# Schematic.net
KiCad netlist of a schematic drawn in EasyEDA
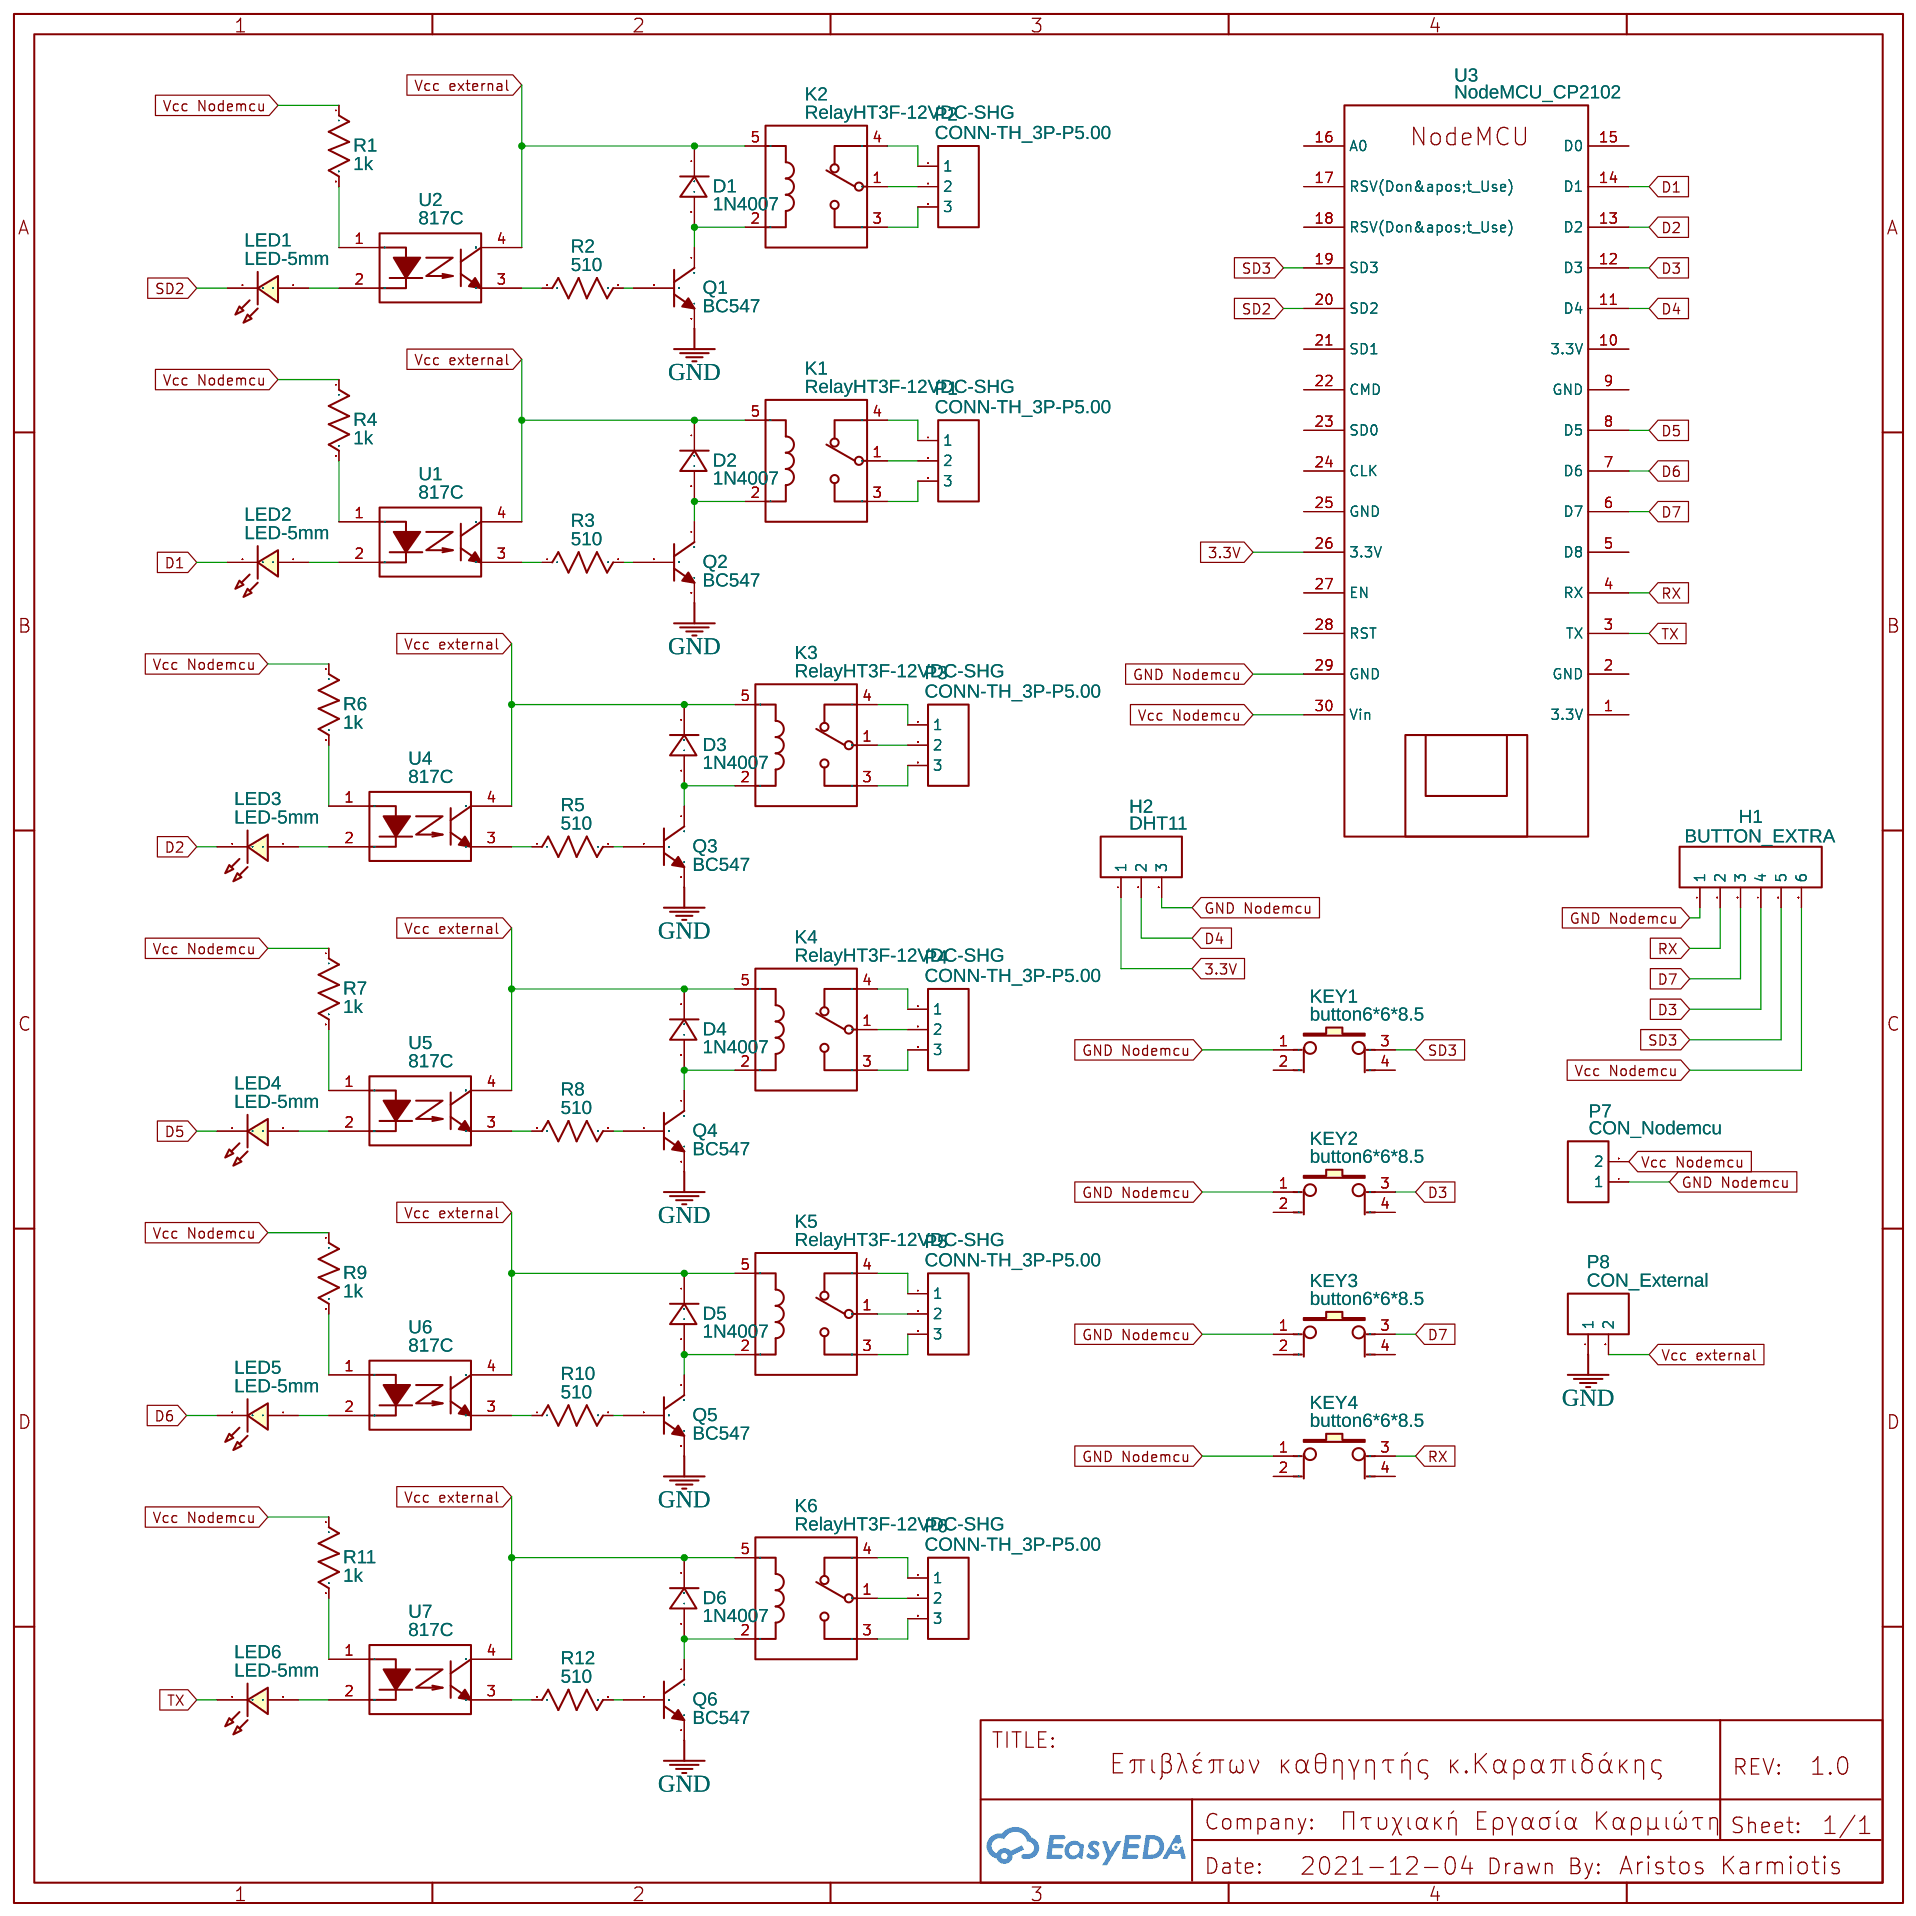
[diagram p0: schematic sheet]

(export (version "E")
  (design (tool "Eeschema 10.0.6"))
  (components
    (comp (ref "D1")
      (value "1N4007")
      (fields (field (name "BOM_Manufacturer Part") "1N4007G-K") (field (name "BOM_Supplier Part") "C410859"))
      (libsource (lib "") (part "1N4007G-K"))
    )
    (comp (ref "D2")
      (value "1N4007")
      (fields (field (name "BOM_Manufacturer Part") "1N4007G-K") (field (name "BOM_Supplier Part") "C410859"))
      (libsource (lib "") (part "1N4007G-K"))
    )
    (comp (ref "D3")
      (value "1N4007")
      (fields (field (name "BOM_Manufacturer Part") "1N4007G-K") (field (name "BOM_Supplier Part") "C410859"))
      (libsource (lib "") (part "1N4007G-K"))
    )
    (comp (ref "D4")
      (value "1N4007")
      (fields (field (name "BOM_Manufacturer Part") "1N4007G-K") (field (name "BOM_Supplier Part") "C410859"))
      (libsource (lib "") (part "1N4007G-K"))
    )
    (comp (ref "D5")
      (value "1N4007")
      (fields (field (name "BOM_Manufacturer Part") "1N4007G-K") (field (name "BOM_Supplier Part") "C410859"))
      (libsource (lib "") (part "1N4007G-K"))
    )
    (comp (ref "D6")
      (value "1N4007")
      (fields (field (name "BOM_Manufacturer Part") "1N4007G-K") (field (name "BOM_Supplier Part") "C410859"))
      (libsource (lib "") (part "1N4007G-K"))
    )
    (comp (ref "H1")
      (value "BUTTON_EXTRA")
      (fields (field (name "BOM_Supplier Part") "C40877"))
      (libsource (lib "") (part "HDR-F-2.54_1x6"))
    )
    (comp (ref "H2")
      (value "DHT11")
      (fields (field (name "BOM_Supplier Part") "C146690"))
      (libsource (lib "") (part "HDR-F-2.54_1x3"))
    )
    (comp (ref "K1")
      (value "RelayHT3F-12VDC-SHG")
      (fields (field (name "BOM_Supplier Part") "C22022"))
      (libsource (lib "") (part "RelayHT3F-12VDC-SHG"))
    )
    (comp (ref "K2")
      (value "RelayHT3F-12VDC-SHG")
      (fields (field (name "BOM_Supplier Part") "C22022"))
      (libsource (lib "") (part "RelayHT3F-12VDC-SHG"))
    )
    (comp (ref "K3")
      (value "RelayHT3F-12VDC-SHG")
      (fields (field (name "BOM_Supplier Part") "C22022"))
      (libsource (lib "") (part "RelayHT3F-12VDC-SHG"))
    )
    (comp (ref "K4")
      (value "RelayHT3F-12VDC-SHG")
      (fields (field (name "BOM_Supplier Part") "C22022"))
      (libsource (lib "") (part "RelayHT3F-12VDC-SHG"))
    )
    (comp (ref "K5")
      (value "RelayHT3F-12VDC-SHG")
      (fields (field (name "BOM_Supplier Part") "C22022"))
      (libsource (lib "") (part "RelayHT3F-12VDC-SHG"))
    )
    (comp (ref "K6")
      (value "RelayHT3F-12VDC-SHG")
      (fields (field (name "BOM_Supplier Part") "C22022"))
      (libsource (lib "") (part "RelayHT3F-12VDC-SHG"))
    )
    (comp (ref "KEY1")
      (value "button6*6*8.5")
      (fields (field (name "BOM_Supplier Part") "C59980"))
      (libsource (lib "") (part "button6*6*8.5"))
    )
    (comp (ref "KEY2")
      (value "button6*6*8.5")
      (fields (field (name "BOM_Supplier Part") "C59980"))
      (libsource (lib "") (part "button6*6*8.5"))
    )
    (comp (ref "KEY3")
      (value "button6*6*8.5")
      (fields (field (name "BOM_Supplier Part") "C59980"))
      (libsource (lib "") (part "button6*6*8.5"))
    )
    (comp (ref "KEY4")
      (value "button6*6*8.5")
      (fields (field (name "BOM_Supplier Part") "C59980"))
      (libsource (lib "") (part "button6*6*8.5"))
    )
    (comp (ref "LED1")
      (value "LED-5mm")
      (fields
        (field (name "BOM_Manufacturer Part") "333-2SURD/S530-A3")
        (field (name "BOM_Supplier Part") "C87271")
      )
      (libsource (lib "") (part "LED-TH-5mm_R"))
    )
    (comp (ref "LED2")
      (value "LED-5mm")
      (fields
        (field (name "BOM_Manufacturer Part") "333-2SURD/S530-A3")
        (field (name "BOM_Supplier Part") "C87271")
      )
      (libsource (lib "") (part "LED-TH-5mm_R"))
    )
    (comp (ref "LED3")
      (value "LED-5mm")
      (fields
        (field (name "BOM_Manufacturer Part") "333-2SURD/S530-A3")
        (field (name "BOM_Supplier Part") "C87271")
      )
      (libsource (lib "") (part "LED-TH-5mm_R"))
    )
    (comp (ref "LED4")
      (value "LED-5mm")
      (fields
        (field (name "BOM_Manufacturer Part") "333-2SURD/S530-A3")
        (field (name "BOM_Supplier Part") "C87271")
      )
      (libsource (lib "") (part "LED-TH-5mm_R"))
    )
    (comp (ref "LED5")
      (value "LED-5mm")
      (fields
        (field (name "BOM_Manufacturer Part") "333-2SURD/S530-A3")
        (field (name "BOM_Supplier Part") "C87271")
      )
      (libsource (lib "") (part "LED-TH-5mm_R"))
    )
    (comp (ref "LED6")
      (value "LED-5mm")
      (fields
        (field (name "BOM_Manufacturer Part") "333-2SURD/S530-A3")
        (field (name "BOM_Supplier Part") "C87271")
      )
      (libsource (lib "") (part "LED-TH-5mm_R"))
    )
    (comp (ref "P1") (value "CONN-TH_3P-P5.00") (libsource (lib "") (part "CONN-TH_3P-P5.00")))
    (comp (ref "P2") (value "CONN-TH_3P-P5.00") (libsource (lib "") (part "CONN-TH_3P-P5.00")))
    (comp (ref "P3") (value "CONN-TH_3P-P5.00") (libsource (lib "") (part "CONN-TH_3P-P5.00")))
    (comp (ref "P4") (value "CONN-TH_3P-P5.00") (libsource (lib "") (part "CONN-TH_3P-P5.00")))
    (comp (ref "P5") (value "CONN-TH_3P-P5.00") (libsource (lib "") (part "CONN-TH_3P-P5.00")))
    (comp (ref "P6") (value "CONN-TH_3P-P5.00") (libsource (lib "") (part "CONN-TH_3P-P5.00")))
    (comp (ref "P7") (value "CON_Nodemcu") (libsource (lib "") (part "CONN-TH_2P-P5.00_1")))
    (comp (ref "P8") (value "CON_External") (libsource (lib "") (part "CONN-TH_2P-P5.00")))
    (comp (ref "Q1")
      (value "BC547")
      (fields (field (name "BOM_Manufacturer Part") "BC547BTF") (field (name "BOM_Supplier Part") "C900798"))
      (libsource (lib "") (part "BC547BTF"))
    )
    (comp (ref "Q2")
      (value "BC547")
      (fields (field (name "BOM_Manufacturer Part") "BC547BTF") (field (name "BOM_Supplier Part") "C900798"))
      (libsource (lib "") (part "BC547BTF"))
    )
    (comp (ref "Q3")
      (value "BC547")
      (fields (field (name "BOM_Manufacturer Part") "BC547BTF") (field (name "BOM_Supplier Part") "C900798"))
      (libsource (lib "") (part "BC547BTF"))
    )
    (comp (ref "Q4")
      (value "BC547")
      (fields (field (name "BOM_Manufacturer Part") "BC547BTF") (field (name "BOM_Supplier Part") "C900798"))
      (libsource (lib "") (part "BC547BTF"))
    )
    (comp (ref "Q5")
      (value "BC547")
      (fields (field (name "BOM_Manufacturer Part") "BC547BTF") (field (name "BOM_Supplier Part") "C900798"))
      (libsource (lib "") (part "BC547BTF"))
    )
    (comp (ref "Q6")
      (value "BC547")
      (fields (field (name "BOM_Manufacturer Part") "BC547BTF") (field (name "BOM_Supplier Part") "C900798"))
      (libsource (lib "") (part "BC547BTF"))
    )
    (comp (ref "R1") (value "1k") (libsource (lib "") (part "R_AXIAL-0.4_US_1")))
    (comp (ref "R2") (value "510") (libsource (lib "") (part "R_AXIAL-0.4_US")))
    (comp (ref "R3") (value "510") (libsource (lib "") (part "R_AXIAL-0.4_US")))
    (comp (ref "R4") (value "1k") (libsource (lib "") (part "R_AXIAL-0.4_US_1")))
    (comp (ref "R5") (value "510") (libsource (lib "") (part "R_AXIAL-0.4_US")))
    (comp (ref "R6") (value "1k") (libsource (lib "") (part "R_AXIAL-0.4_US_1")))
    (comp (ref "R7") (value "1k") (libsource (lib "") (part "R_AXIAL-0.4_US_1")))
    (comp (ref "R8") (value "510") (libsource (lib "") (part "R_AXIAL-0.4_US")))
    (comp (ref "R9") (value "1k") (libsource (lib "") (part "R_AXIAL-0.4_US_1")))
    (comp (ref "R10") (value "510") (libsource (lib "") (part "R_AXIAL-0.4_US")))
    (comp (ref "R11") (value "1k") (libsource (lib "") (part "R_AXIAL-0.4_US_1")))
    (comp (ref "R12") (value "510") (libsource (lib "") (part "R_AXIAL-0.4_US")))
    (comp (ref "U1")
      (value "817C")
      (fields
        (field (name "BOM_Manufacturer Part") "FOD817C300")
        (field (name "BOM_Supplier Part") "C124472")
      )
      (libsource (lib "") (part "FOD817C300"))
    )
    (comp (ref "U2")
      (value "817C")
      (fields
        (field (name "BOM_Manufacturer Part") "FOD817C300")
        (field (name "BOM_Supplier Part") "C124472")
      )
      (libsource (lib "") (part "FOD817C300"))
    )
    (comp (ref "U3") (value "NodeMCU_CP2102") (libsource (lib "") (part "NodeMCU_CP2102")))
    (comp (ref "U4")
      (value "817C")
      (fields
        (field (name "BOM_Manufacturer Part") "FOD817C300")
        (field (name "BOM_Supplier Part") "C124472")
      )
      (libsource (lib "") (part "FOD817C300"))
    )
    (comp (ref "U5")
      (value "817C")
      (fields
        (field (name "BOM_Manufacturer Part") "FOD817C300")
        (field (name "BOM_Supplier Part") "C124472")
      )
      (libsource (lib "") (part "FOD817C300"))
    )
    (comp (ref "U6")
      (value "817C")
      (fields
        (field (name "BOM_Manufacturer Part") "FOD817C300")
        (field (name "BOM_Supplier Part") "C124472")
      )
      (libsource (lib "") (part "FOD817C300"))
    )
    (comp (ref "U7")
      (value "817C")
      (fields
        (field (name "BOM_Manufacturer Part") "FOD817C300")
        (field (name "BOM_Supplier Part") "C124472")
      )
      (libsource (lib "") (part "FOD817C300"))
    )
  )
  (nets
    (net (code "1") (name "3.3V") (class "Default")
      (node (ref "H2") (pin "1") (pinfunction "1_1") (pintype "input"))
      (node (ref "U3") (pin "26") (pinfunction "3.3V_26") (pintype "unspecified"))
    )
    (net (code "2") (name "D1") (class "Default")
      (node (ref "LED2") (pin "2") (pinfunction "2_2") (pintype "unspecified"))
      (node (ref "U3") (pin "14") (pinfunction "D1_14") (pintype "unspecified"))
    )
    (net (code "3") (name "D2") (class "Default")
      (node (ref "LED3") (pin "2") (pinfunction "2_2") (pintype "unspecified"))
      (node (ref "U3") (pin "13") (pinfunction "D2_13") (pintype "unspecified"))
    )
    (net (code "4") (name "D3") (class "Default")
      (node (ref "H1") (pin "4") (pinfunction "4_4") (pintype "input"))
      (node (ref "KEY2") (pin "3") (pinfunction "3_3") (pintype "input"))
      (node (ref "U3") (pin "12") (pinfunction "D3_12") (pintype "unspecified"))
    )
    (net (code "5") (name "D4") (class "Default")
      (node (ref "H2") (pin "2") (pinfunction "2_2") (pintype "input"))
      (node (ref "U3") (pin "11") (pinfunction "D4_11") (pintype "unspecified"))
    )
    (net (code "6") (name "D5") (class "Default")
      (node (ref "LED4") (pin "2") (pinfunction "2_2") (pintype "unspecified"))
      (node (ref "U3") (pin "8") (pinfunction "D5_8") (pintype "unspecified"))
    )
    (net (code "7") (name "D6") (class "Default")
      (node (ref "LED5") (pin "2") (pinfunction "2_2") (pintype "unspecified"))
      (node (ref "U3") (pin "7") (pinfunction "D6_7") (pintype "unspecified"))
    )
    (net (code "8") (name "D7") (class "Default")
      (node (ref "H1") (pin "3") (pinfunction "3_3") (pintype "input"))
      (node (ref "KEY3") (pin "3") (pinfunction "3_3") (pintype "input"))
      (node (ref "U3") (pin "6") (pinfunction "D7_6") (pintype "unspecified"))
    )
    (net (code "9") (name "GND") (class "Default")
      (node (ref "P8") (pin "1") (pinfunction "1_1") (pintype "unspecified"))
      (node (ref "Q1") (pin "3") (pinfunction "E_3") (pintype "unspecified"))
      (node (ref "Q2") (pin "3") (pinfunction "E_3") (pintype "unspecified"))
      (node (ref "Q3") (pin "3") (pinfunction "E_3") (pintype "unspecified"))
      (node (ref "Q4") (pin "3") (pinfunction "E_3") (pintype "unspecified"))
      (node (ref "Q5") (pin "3") (pinfunction "E_3") (pintype "unspecified"))
      (node (ref "Q6") (pin "3") (pinfunction "E_3") (pintype "unspecified"))
    )
    (net (code "10") (name "GND Nodemcu") (class "Default")
      (node (ref "H1") (pin "1") (pinfunction "1_1") (pintype "input"))
      (node (ref "H2") (pin "3") (pinfunction "3_3") (pintype "input"))
      (node (ref "KEY1") (pin "1") (pinfunction "1_1") (pintype "input"))
      (node (ref "KEY2") (pin "1") (pinfunction "1_1") (pintype "input"))
      (node (ref "KEY3") (pin "1") (pinfunction "1_1") (pintype "input"))
      (node (ref "KEY4") (pin "1") (pinfunction "1_1") (pintype "input"))
      (node (ref "P7") (pin "1") (pinfunction "1_1") (pintype "unspecified"))
      (node (ref "U3") (pin "29") (pinfunction "GND_29") (pintype "unspecified"))
    )
    (net (code "11") (name "Net-(D1-A)") (class "Default")
      (node (ref "D1") (pin "2") (pinfunction "A_2") (pintype "unspecified"))
      (node (ref "K2") (pin "2") (pinfunction "2_2") (pintype "unspecified"))
      (node (ref "Q1") (pin "1") (pinfunction "C_1") (pintype "unspecified"))
    )
    (net (code "12") (name "Net-(D2-A)") (class "Default")
      (node (ref "D2") (pin "2") (pinfunction "A_2") (pintype "unspecified"))
      (node (ref "K1") (pin "2") (pinfunction "2_2") (pintype "unspecified"))
      (node (ref "Q2") (pin "1") (pinfunction "C_1") (pintype "unspecified"))
    )
    (net (code "13") (name "Net-(D3-A)") (class "Default")
      (node (ref "D3") (pin "2") (pinfunction "A_2") (pintype "unspecified"))
      (node (ref "K3") (pin "2") (pinfunction "2_2") (pintype "unspecified"))
      (node (ref "Q3") (pin "1") (pinfunction "C_1") (pintype "unspecified"))
    )
    (net (code "14") (name "Net-(D4-A)") (class "Default")
      (node (ref "D4") (pin "2") (pinfunction "A_2") (pintype "unspecified"))
      (node (ref "K4") (pin "2") (pinfunction "2_2") (pintype "unspecified"))
      (node (ref "Q4") (pin "1") (pinfunction "C_1") (pintype "unspecified"))
    )
    (net (code "15") (name "Net-(D5-A)") (class "Default")
      (node (ref "D5") (pin "2") (pinfunction "A_2") (pintype "unspecified"))
      (node (ref "K5") (pin "2") (pinfunction "2_2") (pintype "unspecified"))
      (node (ref "Q5") (pin "1") (pinfunction "C_1") (pintype "unspecified"))
    )
    (net (code "16") (name "Net-(D6-A)") (class "Default")
      (node (ref "D6") (pin "2") (pinfunction "A_2") (pintype "unspecified"))
      (node (ref "K6") (pin "2") (pinfunction "2_2") (pintype "unspecified"))
      (node (ref "Q6") (pin "1") (pinfunction "C_1") (pintype "unspecified"))
    )
    (net (code "17") (name "Net-(K1-Pad1)") (class "Default")
      (node (ref "K1") (pin "1") (pinfunction "1_1") (pintype "unspecified"))
      (node (ref "P1") (pin "2") (pinfunction "2_2") (pintype "unspecified"))
    )
    (net (code "18") (name "Net-(K1-Pad3)") (class "Default")
      (node (ref "K1") (pin "3") (pinfunction "3_3") (pintype "unspecified"))
      (node (ref "P1") (pin "3") (pinfunction "3_3") (pintype "unspecified"))
    )
    (net (code "19") (name "Net-(K1-Pad4)") (class "Default")
      (node (ref "K1") (pin "4") (pinfunction "4_4") (pintype "unspecified"))
      (node (ref "P1") (pin "1") (pinfunction "1_1") (pintype "unspecified"))
    )
    (net (code "20") (name "Net-(K2-Pad1)") (class "Default")
      (node (ref "K2") (pin "1") (pinfunction "1_1") (pintype "unspecified"))
      (node (ref "P2") (pin "2") (pinfunction "2_2") (pintype "unspecified"))
    )
    (net (code "21") (name "Net-(K2-Pad3)") (class "Default")
      (node (ref "K2") (pin "3") (pinfunction "3_3") (pintype "unspecified"))
      (node (ref "P2") (pin "3") (pinfunction "3_3") (pintype "unspecified"))
    )
    (net (code "22") (name "Net-(K2-Pad4)") (class "Default")
      (node (ref "K2") (pin "4") (pinfunction "4_4") (pintype "unspecified"))
      (node (ref "P2") (pin "1") (pinfunction "1_1") (pintype "unspecified"))
    )
    (net (code "23") (name "Net-(K3-Pad1)") (class "Default")
      (node (ref "K3") (pin "1") (pinfunction "1_1") (pintype "unspecified"))
      (node (ref "P3") (pin "2") (pinfunction "2_2") (pintype "unspecified"))
    )
    (net (code "24") (name "Net-(K3-Pad3)") (class "Default")
      (node (ref "K3") (pin "3") (pinfunction "3_3") (pintype "unspecified"))
      (node (ref "P3") (pin "3") (pinfunction "3_3") (pintype "unspecified"))
    )
    (net (code "25") (name "Net-(K3-Pad4)") (class "Default")
      (node (ref "K3") (pin "4") (pinfunction "4_4") (pintype "unspecified"))
      (node (ref "P3") (pin "1") (pinfunction "1_1") (pintype "unspecified"))
    )
    (net (code "26") (name "Net-(K4-Pad1)") (class "Default")
      (node (ref "K4") (pin "1") (pinfunction "1_1") (pintype "unspecified"))
      (node (ref "P4") (pin "2") (pinfunction "2_2") (pintype "unspecified"))
    )
    (net (code "27") (name "Net-(K4-Pad3)") (class "Default")
      (node (ref "K4") (pin "3") (pinfunction "3_3") (pintype "unspecified"))
      (node (ref "P4") (pin "3") (pinfunction "3_3") (pintype "unspecified"))
    )
    (net (code "28") (name "Net-(K4-Pad4)") (class "Default")
      (node (ref "K4") (pin "4") (pinfunction "4_4") (pintype "unspecified"))
      (node (ref "P4") (pin "1") (pinfunction "1_1") (pintype "unspecified"))
    )
    (net (code "29") (name "Net-(K5-Pad1)") (class "Default")
      (node (ref "K5") (pin "1") (pinfunction "1_1") (pintype "unspecified"))
      (node (ref "P5") (pin "2") (pinfunction "2_2") (pintype "unspecified"))
    )
    (net (code "30") (name "Net-(K5-Pad3)") (class "Default")
      (node (ref "K5") (pin "3") (pinfunction "3_3") (pintype "unspecified"))
      (node (ref "P5") (pin "3") (pinfunction "3_3") (pintype "unspecified"))
    )
    (net (code "31") (name "Net-(K5-Pad4)") (class "Default")
      (node (ref "K5") (pin "4") (pinfunction "4_4") (pintype "unspecified"))
      (node (ref "P5") (pin "1") (pinfunction "1_1") (pintype "unspecified"))
    )
    (net (code "32") (name "Net-(K6-Pad1)") (class "Default")
      (node (ref "K6") (pin "1") (pinfunction "1_1") (pintype "unspecified"))
      (node (ref "P6") (pin "2") (pinfunction "2_2") (pintype "unspecified"))
    )
    (net (code "33") (name "Net-(K6-Pad3)") (class "Default")
      (node (ref "K6") (pin "3") (pinfunction "3_3") (pintype "unspecified"))
      (node (ref "P6") (pin "3") (pinfunction "3_3") (pintype "unspecified"))
    )
    (net (code "34") (name "Net-(K6-Pad4)") (class "Default")
      (node (ref "K6") (pin "4") (pinfunction "4_4") (pintype "unspecified"))
      (node (ref "P6") (pin "1") (pinfunction "1_1") (pintype "unspecified"))
    )
    (net (code "35") (name "Net-(Q1-B)") (class "Default")
      (node (ref "Q1") (pin "2") (pinfunction "B_2") (pintype "unspecified"))
      (node (ref "R2") (pin "2") (pinfunction "2_2") (pintype "unspecified"))
    )
    (net (code "36") (name "Net-(Q2-B)") (class "Default")
      (node (ref "Q2") (pin "2") (pinfunction "B_2") (pintype "unspecified"))
      (node (ref "R3") (pin "2") (pinfunction "2_2") (pintype "unspecified"))
    )
    (net (code "37") (name "Net-(Q3-B)") (class "Default")
      (node (ref "Q3") (pin "2") (pinfunction "B_2") (pintype "unspecified"))
      (node (ref "R5") (pin "2") (pinfunction "2_2") (pintype "unspecified"))
    )
    (net (code "38") (name "Net-(Q4-B)") (class "Default")
      (node (ref "Q4") (pin "2") (pinfunction "B_2") (pintype "unspecified"))
      (node (ref "R8") (pin "2") (pinfunction "2_2") (pintype "unspecified"))
    )
    (net (code "39") (name "Net-(Q5-B)") (class "Default")
      (node (ref "Q5") (pin "2") (pinfunction "B_2") (pintype "unspecified"))
      (node (ref "R10") (pin "2") (pinfunction "2_2") (pintype "unspecified"))
    )
    (net (code "40") (name "Net-(Q6-B)") (class "Default")
      (node (ref "Q6") (pin "2") (pinfunction "B_2") (pintype "unspecified"))
      (node (ref "R12") (pin "2") (pinfunction "2_2") (pintype "unspecified"))
    )
    (net (code "41") (name "Net-(U1-AN)") (class "Default")
      (node (ref "R4") (pin "2") (pinfunction "2_2") (pintype "unspecified"))
      (node (ref "U1") (pin "1") (pinfunction "AN_1") (pintype "unspecified"))
    )
    (net (code "42") (name "Net-(U1-CAT)") (class "Default")
      (node (ref "LED2") (pin "1") (pinfunction "1_1") (pintype "unspecified"))
      (node (ref "U1") (pin "2") (pinfunction "CAT_2") (pintype "unspecified"))
    )
    (net (code "43") (name "Net-(U1-EM)") (class "Default")
      (node (ref "R3") (pin "1") (pinfunction "1_1") (pintype "unspecified"))
      (node (ref "U1") (pin "3") (pinfunction "EM_3") (pintype "unspecified"))
    )
    (net (code "44") (name "Net-(U2-AN)") (class "Default")
      (node (ref "R1") (pin "2") (pinfunction "2_2") (pintype "unspecified"))
      (node (ref "U2") (pin "1") (pinfunction "AN_1") (pintype "unspecified"))
    )
    (net (code "45") (name "Net-(U2-CAT)") (class "Default")
      (node (ref "LED1") (pin "1") (pinfunction "1_1") (pintype "unspecified"))
      (node (ref "U2") (pin "2") (pinfunction "CAT_2") (pintype "unspecified"))
    )
    (net (code "46") (name "Net-(U2-EM)") (class "Default")
      (node (ref "R2") (pin "1") (pinfunction "1_1") (pintype "unspecified"))
      (node (ref "U2") (pin "3") (pinfunction "EM_3") (pintype "unspecified"))
    )
    (net (code "47") (name "Net-(U4-AN)") (class "Default")
      (node (ref "R6") (pin "2") (pinfunction "2_2") (pintype "unspecified"))
      (node (ref "U4") (pin "1") (pinfunction "AN_1") (pintype "unspecified"))
    )
    (net (code "48") (name "Net-(U4-CAT)") (class "Default")
      (node (ref "LED3") (pin "1") (pinfunction "1_1") (pintype "unspecified"))
      (node (ref "U4") (pin "2") (pinfunction "CAT_2") (pintype "unspecified"))
    )
    (net (code "49") (name "Net-(U4-EM)") (class "Default")
      (node (ref "R5") (pin "1") (pinfunction "1_1") (pintype "unspecified"))
      (node (ref "U4") (pin "3") (pinfunction "EM_3") (pintype "unspecified"))
    )
    (net (code "50") (name "Net-(U5-AN)") (class "Default")
      (node (ref "R7") (pin "2") (pinfunction "2_2") (pintype "unspecified"))
      (node (ref "U5") (pin "1") (pinfunction "AN_1") (pintype "unspecified"))
    )
    (net (code "51") (name "Net-(U5-CAT)") (class "Default")
      (node (ref "LED4") (pin "1") (pinfunction "1_1") (pintype "unspecified"))
      (node (ref "U5") (pin "2") (pinfunction "CAT_2") (pintype "unspecified"))
    )
    (net (code "52") (name "Net-(U5-EM)") (class "Default")
      (node (ref "R8") (pin "1") (pinfunction "1_1") (pintype "unspecified"))
      (node (ref "U5") (pin "3") (pinfunction "EM_3") (pintype "unspecified"))
    )
    (net (code "53") (name "Net-(U6-AN)") (class "Default")
      (node (ref "R9") (pin "2") (pinfunction "2_2") (pintype "unspecified"))
      (node (ref "U6") (pin "1") (pinfunction "AN_1") (pintype "unspecified"))
    )
    (net (code "54") (name "Net-(U6-CAT)") (class "Default")
      (node (ref "LED5") (pin "1") (pinfunction "1_1") (pintype "unspecified"))
      (node (ref "U6") (pin "2") (pinfunction "CAT_2") (pintype "unspecified"))
    )
    (net (code "55") (name "Net-(U6-EM)") (class "Default")
      (node (ref "R10") (pin "1") (pinfunction "1_1") (pintype "unspecified"))
      (node (ref "U6") (pin "3") (pinfunction "EM_3") (pintype "unspecified"))
    )
    (net (code "56") (name "Net-(U7-AN)") (class "Default")
      (node (ref "R11") (pin "2") (pinfunction "2_2") (pintype "unspecified"))
      (node (ref "U7") (pin "1") (pinfunction "AN_1") (pintype "unspecified"))
    )
    (net (code "57") (name "Net-(U7-CAT)") (class "Default")
      (node (ref "LED6") (pin "1") (pinfunction "1_1") (pintype "unspecified"))
      (node (ref "U7") (pin "2") (pinfunction "CAT_2") (pintype "unspecified"))
    )
    (net (code "58") (name "Net-(U7-EM)") (class "Default")
      (node (ref "R12") (pin "1") (pinfunction "1_1") (pintype "unspecified"))
      (node (ref "U7") (pin "3") (pinfunction "EM_3") (pintype "unspecified"))
    )
    (net (code "59") (name "RX") (class "Default")
      (node (ref "H1") (pin "2") (pinfunction "2_2") (pintype "input"))
      (node (ref "KEY4") (pin "3") (pinfunction "3_3") (pintype "input"))
      (node (ref "U3") (pin "4") (pinfunction "RX_4") (pintype "unspecified"))
    )
    (net (code "60") (name "SD2") (class "Default")
      (node (ref "LED1") (pin "2") (pinfunction "2_2") (pintype "unspecified"))
      (node (ref "U3") (pin "20") (pinfunction "SD2_20") (pintype "unspecified"))
    )
    (net (code "61") (name "SD3") (class "Default")
      (node (ref "H1") (pin "5") (pinfunction "5_5") (pintype "input"))
      (node (ref "KEY1") (pin "3") (pinfunction "3_3") (pintype "input"))
      (node (ref "U3") (pin "19") (pinfunction "SD3_19") (pintype "unspecified"))
    )
    (net (code "62") (name "TX") (class "Default")
      (node (ref "LED6") (pin "2") (pinfunction "2_2") (pintype "unspecified"))
      (node (ref "U3") (pin "3") (pinfunction "TX_3") (pintype "unspecified"))
    )
    (net (code "63") (name "Vcc Nodemcu") (class "Default")
      (node (ref "H1") (pin "6") (pinfunction "6_6") (pintype "input"))
      (node (ref "P7") (pin "2") (pinfunction "2_2") (pintype "unspecified"))
      (node (ref "R1") (pin "1") (pinfunction "1_1") (pintype "unspecified"))
      (node (ref "R11") (pin "1") (pinfunction "1_1") (pintype "unspecified"))
      (node (ref "R4") (pin "1") (pinfunction "1_1") (pintype "unspecified"))
      (node (ref "R6") (pin "1") (pinfunction "1_1") (pintype "unspecified"))
      (node (ref "R7") (pin "1") (pinfunction "1_1") (pintype "unspecified"))
      (node (ref "R9") (pin "1") (pinfunction "1_1") (pintype "unspecified"))
      (node (ref "U3") (pin "30") (pinfunction "Vin_30") (pintype "unspecified"))
    )
    (net (code "64") (name "Vcc external") (class "Default")
      (node (ref "D1") (pin "1") (pinfunction "C_1") (pintype "unspecified"))
      (node (ref "D2") (pin "1") (pinfunction "C_1") (pintype "unspecified"))
      (node (ref "D3") (pin "1") (pinfunction "C_1") (pintype "unspecified"))
      (node (ref "D4") (pin "1") (pinfunction "C_1") (pintype "unspecified"))
      (node (ref "D5") (pin "1") (pinfunction "C_1") (pintype "unspecified"))
      (node (ref "D6") (pin "1") (pinfunction "C_1") (pintype "unspecified"))
      (node (ref "K1") (pin "5") (pinfunction "5_5") (pintype "unspecified"))
      (node (ref "K2") (pin "5") (pinfunction "5_5") (pintype "unspecified"))
      (node (ref "K3") (pin "5") (pinfunction "5_5") (pintype "unspecified"))
      (node (ref "K4") (pin "5") (pinfunction "5_5") (pintype "unspecified"))
      (node (ref "K5") (pin "5") (pinfunction "5_5") (pintype "unspecified"))
      (node (ref "K6") (pin "5") (pinfunction "5_5") (pintype "unspecified"))
      (node (ref "P8") (pin "2") (pinfunction "2_2") (pintype "unspecified"))
      (node (ref "U1") (pin "4") (pinfunction "COL_4") (pintype "unspecified"))
      (node (ref "U2") (pin "4") (pinfunction "COL_4") (pintype "unspecified"))
      (node (ref "U4") (pin "4") (pinfunction "COL_4") (pintype "unspecified"))
      (node (ref "U5") (pin "4") (pinfunction "COL_4") (pintype "unspecified"))
      (node (ref "U6") (pin "4") (pinfunction "COL_4") (pintype "unspecified"))
      (node (ref "U7") (pin "4") (pinfunction "COL_4") (pintype "unspecified"))
    )
    (net (code "65") (name "unconnected-(KEY1-Pad2)") (class "Default")
      (node (ref "KEY1") (pin "2") (pinfunction "2_2") (pintype "input"))
    )
    (net (code "66") (name "unconnected-(KEY1-Pad4)") (class "Default")
      (node (ref "KEY1") (pin "4") (pinfunction "4_4") (pintype "input"))
    )
    (net (code "67") (name "unconnected-(KEY2-Pad2)") (class "Default")
      (node (ref "KEY2") (pin "2") (pinfunction "2_2") (pintype "input"))
    )
    (net (code "68") (name "unconnected-(KEY2-Pad4)") (class "Default")
      (node (ref "KEY2") (pin "4") (pinfunction "4_4") (pintype "input"))
    )
    (net (code "69") (name "unconnected-(KEY3-Pad2)") (class "Default")
      (node (ref "KEY3") (pin "2") (pinfunction "2_2") (pintype "input"))
    )
    (net (code "70") (name "unconnected-(KEY3-Pad4)") (class "Default")
      (node (ref "KEY3") (pin "4") (pinfunction "4_4") (pintype "input"))
    )
    (net (code "71") (name "unconnected-(KEY4-Pad2)") (class "Default")
      (node (ref "KEY4") (pin "2") (pinfunction "2_2") (pintype "input"))
    )
    (net (code "72") (name "unconnected-(KEY4-Pad4)") (class "Default")
      (node (ref "KEY4") (pin "4") (pinfunction "4_4") (pintype "input"))
    )
    (net (code "73") (name "unconnected-(U3-3.3V-Pad1)") (class "Default")
      (node (ref "U3") (pin "1") (pinfunction "3.3V_1") (pintype "unspecified"))
    )
    (net (code "74") (name "unconnected-(U3-3.3V-Pad10)") (class "Default")
      (node (ref "U3") (pin "10") (pinfunction "3.3V_10") (pintype "unspecified"))
    )
    (net (code "75") (name "unconnected-(U3-A0-Pad16)") (class "Default")
      (node (ref "U3") (pin "16") (pinfunction "A0_16") (pintype "unspecified"))
    )
    (net (code "76") (name "unconnected-(U3-CLK-Pad24)") (class "Default")
      (node (ref "U3") (pin "24") (pinfunction "CLK_24") (pintype "unspecified"))
    )
    (net (code "77") (name "unconnected-(U3-CMD-Pad22)") (class "Default")
      (node (ref "U3") (pin "22") (pinfunction "CMD_22") (pintype "unspecified"))
    )
    (net (code "78") (name "unconnected-(U3-D0-Pad15)") (class "Default")
      (node (ref "U3") (pin "15") (pinfunction "D0_15") (pintype "unspecified"))
    )
    (net (code "79") (name "unconnected-(U3-D8-Pad5)") (class "Default")
      (node (ref "U3") (pin "5") (pinfunction "D8_5") (pintype "unspecified"))
    )
    (net (code "80") (name "unconnected-(U3-EN-Pad27)") (class "Default")
      (node (ref "U3") (pin "27") (pinfunction "EN_27") (pintype "unspecified"))
    )
    (net (code "81") (name "unconnected-(U3-GND-Pad2)") (class "Default")
      (node (ref "U3") (pin "2") (pinfunction "GND_2") (pintype "unspecified"))
    )
    (net (code "82") (name "unconnected-(U3-GND-Pad9)") (class "Default")
      (node (ref "U3") (pin "9") (pinfunction "GND_9") (pintype "unspecified"))
    )
    (net (code "83") (name "unconnected-(U3-GND-Pad25)") (class "Default")
      (node (ref "U3") (pin "25") (pinfunction "GND_25") (pintype "unspecified"))
    )
    (net (code "84") (name "unconnected-(U3-RST-Pad28)") (class "Default")
      (node (ref "U3") (pin "28") (pinfunction "RST_28") (pintype "unspecified"))
    )
    (net (code "85") (name "unconnected-(U3-RSV(Don&apos;t_Use)-Pad17)") (class "Default")
      (node (ref "U3") (pin "17") (pinfunction "RSV(Don&apos;t_Use)_17") (pintype "unspecified"))
    )
    (net (code "86") (name "unconnected-(U3-RSV(Don&apos;t_Use)-Pad18)") (class "Default")
      (node (ref "U3") (pin "18") (pinfunction "RSV(Don&apos;t_Use)_18") (pintype "unspecified"))
    )
    (net (code "87") (name "unconnected-(U3-SD0-Pad23)") (class "Default")
      (node (ref "U3") (pin "23") (pinfunction "SD0_23") (pintype "unspecified"))
    )
    (net (code "88") (name "unconnected-(U3-SD1-Pad21)") (class "Default")
      (node (ref "U3") (pin "21") (pinfunction "SD1_21") (pintype "unspecified"))
    )
  )
)
